# ETHERNET.net
KiCad netlist of a schematic drawn in Altium Designer
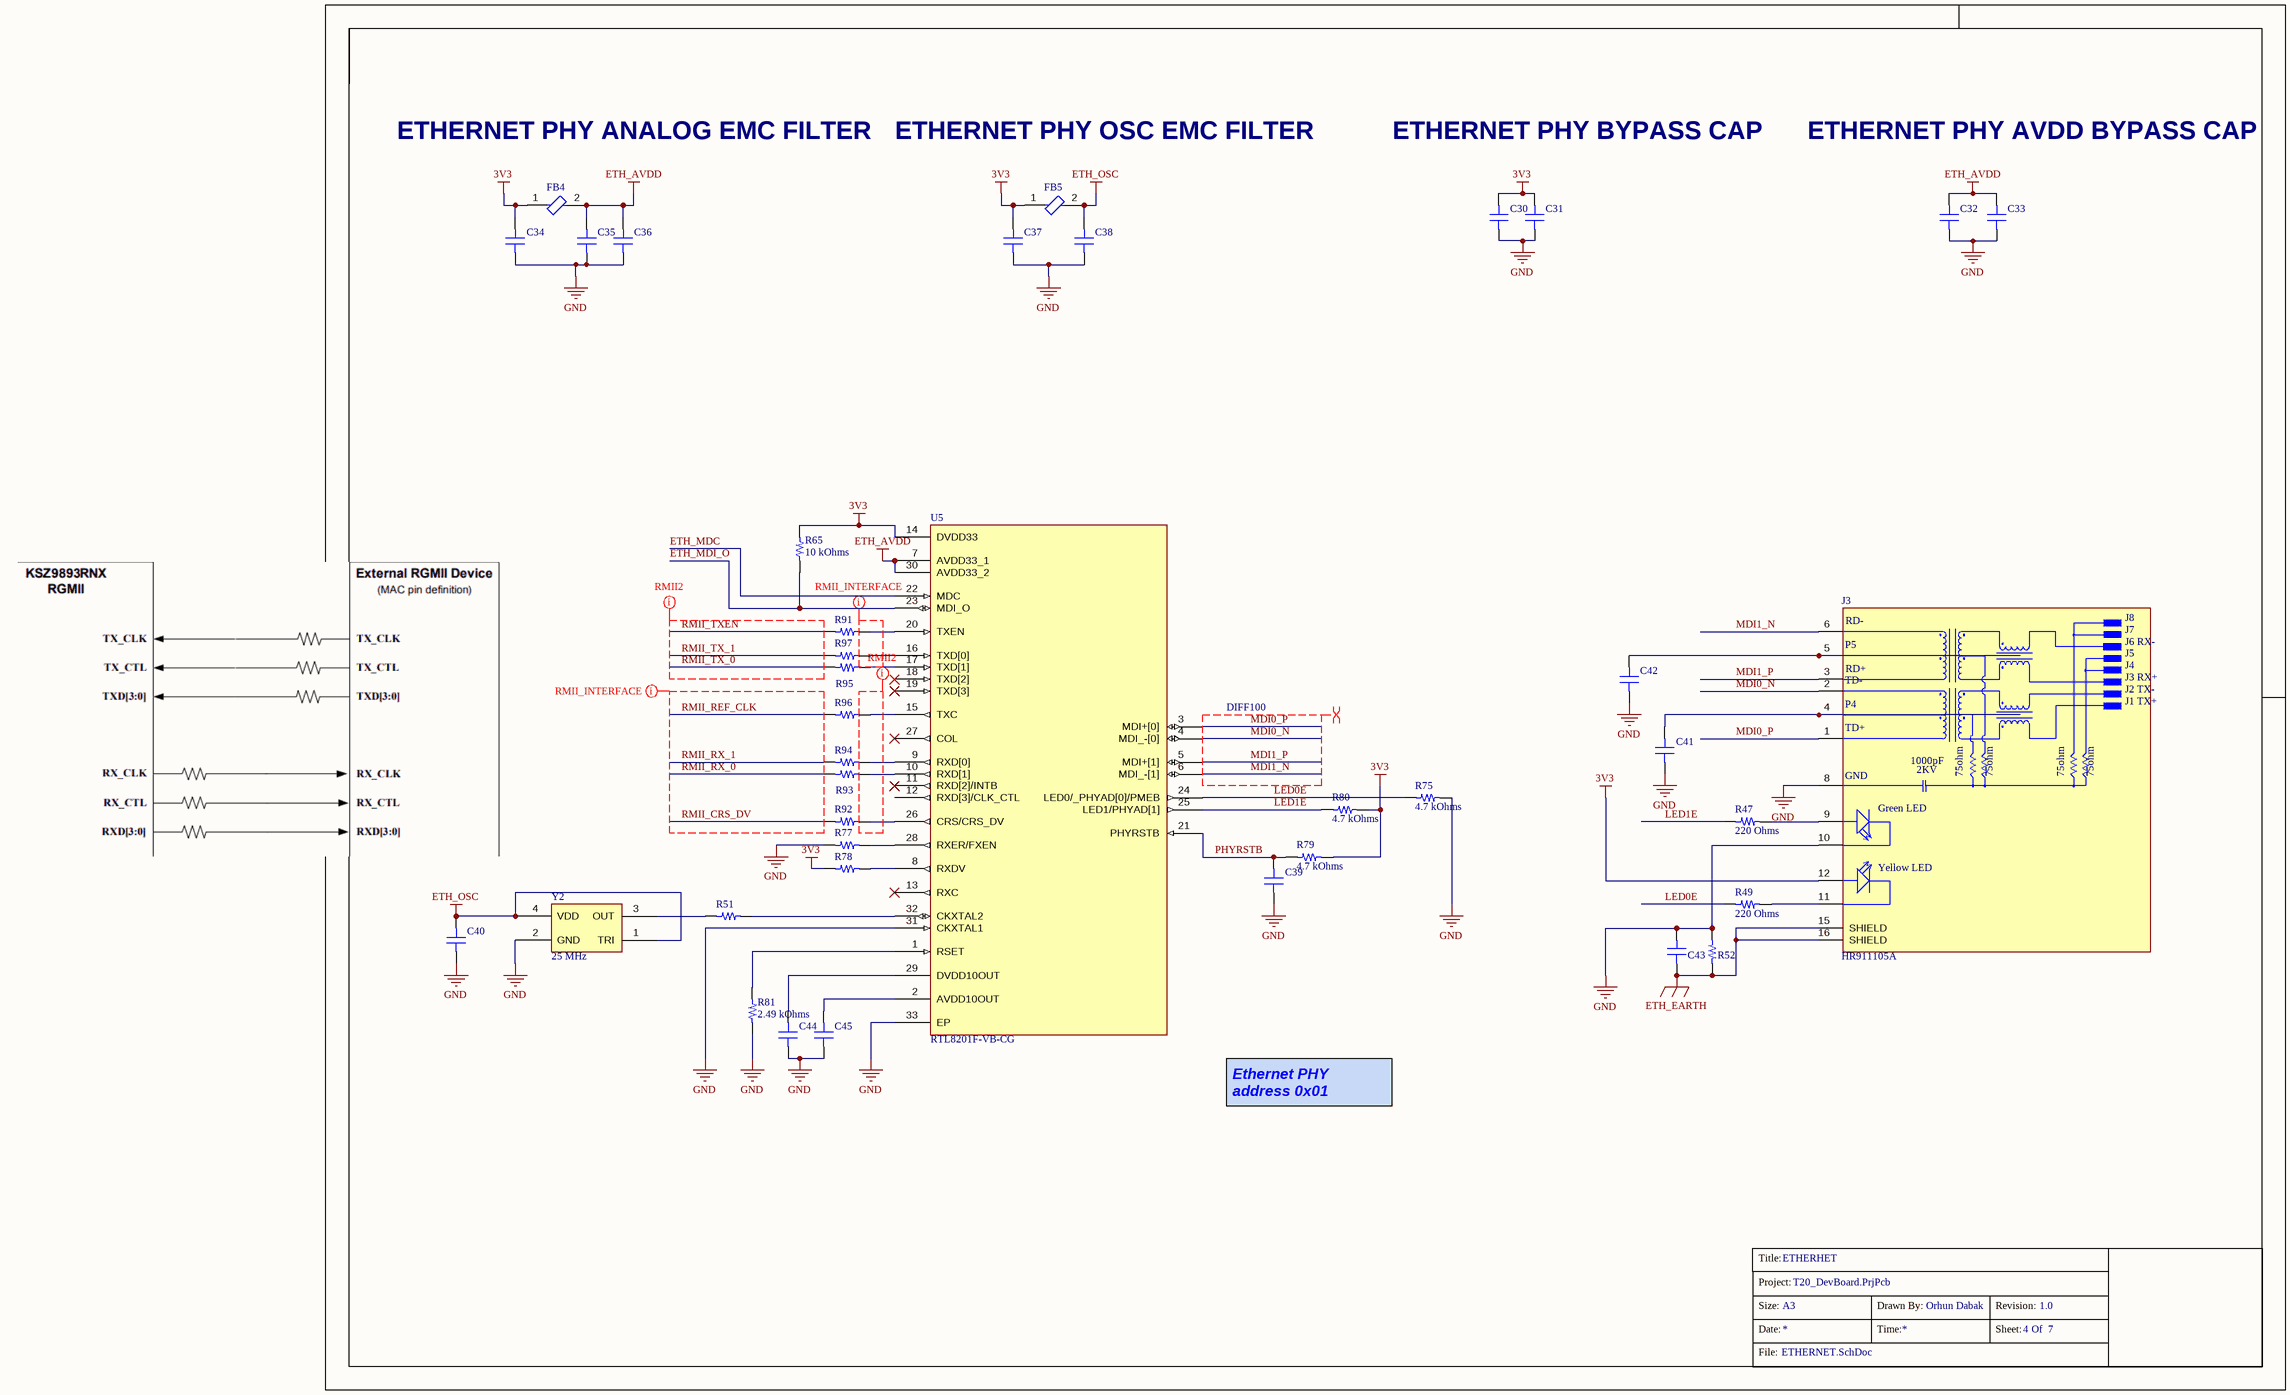
[diagram p0: ETHERNET.SchDoc]

(export (version "E")
  (design (tool "Eeschema 10.0.6"))
  (components
    (comp (ref "C30")
      (value "0.1 µF")
      (footprint "CAP 0402_1005")
      (description "CAP CER 0.1UF 10V X7R 0402")
      (fields (field (name "PART NUMBER") "CC0402KRX7R6BB104") (field (name "MANUFACTURER") "Yageo"))
      (libsource (lib "Celestial Altium Library - altium_library") (part "Capacitor"))
    )
    (comp (ref "C31")
      (value "2.2 µF")
      (footprint "CAP 0402_1005")
      (description "CAP CER 2.2UF 10V X5R 0402")
      (fields (field (name "PART NUMBER") "C0402C225M8PAC7867") (field (name "MANUFACTURER") "KEMET"))
      (libsource (lib "Celestial Altium Library - altium_library") (part "Capacitor"))
    )
    (comp (ref "C32")
      (value "0.1 µF")
      (footprint "CAP 0402_1005")
      (description "CAP CER 0.1UF 10V X7R 0402")
      (fields (field (name "PART NUMBER") "CC0402KRX7R6BB104") (field (name "MANUFACTURER") "Yageo"))
      (libsource (lib "Celestial Altium Library - altium_library") (part "Capacitor"))
    )
    (comp (ref "C33")
      (value "0.1 µF")
      (footprint "CAP 0402_1005")
      (description "CAP CER 0.1UF 10V X7R 0402")
      (fields (field (name "PART NUMBER") "CC0402KRX7R6BB104") (field (name "MANUFACTURER") "Yageo"))
      (libsource (lib "Celestial Altium Library - altium_library") (part "Capacitor"))
    )
    (comp (ref "C34")
      (value "0.1 µF")
      (footprint "CAP 0402_1005")
      (description "CAP CER 0.1UF 10V X7R 0402")
      (fields (field (name "PART NUMBER") "CC0402KRX7R6BB104") (field (name "MANUFACTURER") "Yageo"))
      (libsource (lib "Celestial Altium Library - altium_library") (part "Capacitor"))
    )
    (comp (ref "C35")
      (value "0.1 µF")
      (footprint "CAP 0402_1005")
      (description "CAP CER 0.1UF 10V X7R 0402")
      (fields (field (name "PART NUMBER") "CC0402KRX7R6BB104") (field (name "MANUFACTURER") "Yageo"))
      (libsource (lib "Celestial Altium Library - altium_library") (part "Capacitor"))
    )
    (comp (ref "C36")
      (value "4.7 µF")
      (footprint "CAP 0402_1005")
      (description "CAP CER 4.7UF 10V X5R 0402")
      (fields
        (field (name "PART NUMBER") "CL05A475MP5NRNC")
        (field (name "MANUFACTURER") "Samsung Electro-Mechanics")
      )
      (libsource (lib "Celestial Altium Library - altium_library") (part "Capacitor"))
    )
    (comp (ref "C37")
      (value "4.7 µF")
      (footprint "CAP 0402_1005")
      (description "CAP CER 4.7UF 10V X5R 0402")
      (fields
        (field (name "PART NUMBER") "CL05A475MP5NRNC")
        (field (name "MANUFACTURER") "Samsung Electro-Mechanics")
      )
      (libsource (lib "Celestial Altium Library - altium_library") (part "Capacitor"))
    )
    (comp (ref "C38")
      (value "4.7 µF")
      (footprint "CAP 0402_1005")
      (description "CAP CER 4.7UF 10V X5R 0402")
      (fields
        (field (name "PART NUMBER") "CL05A475MP5NRNC")
        (field (name "MANUFACTURER") "Samsung Electro-Mechanics")
      )
      (libsource (lib "Celestial Altium Library - altium_library") (part "Capacitor"))
    )
    (comp (ref "C39")
      (value "1000pF")
      (footprint "CAP 0402_1005")
      (description "CAP CER 1000PF 10V X7R 0402")
      (fields (field (name "PART NUMBER") "0402ZC102KAT2A") (field (name "MANUFACTURER") "AVX Corporation"))
      (libsource (lib "Celestial Altium Library - altium_library") (part "Capacitor"))
    )
    (comp (ref "C40")
      (value "0.1 µF")
      (footprint "CAP 0402_1005")
      (description "CAP CER 0.1UF 10V X7R 0402")
      (fields (field (name "PART NUMBER") "CC0402KRX7R6BB104") (field (name "MANUFACTURER") "Yageo"))
      (libsource (lib "Celestial Altium Library - altium_library") (part "Capacitor"))
    )
    (comp (ref "C41")
      (value "10000 pF")
      (footprint "CAP 0402_1005")
      (description "CAP CER 0402 10NF 50V X7R 10%")
      (fields (field (name "PART NUMBER") "C0402C103K5RECAUTO") (field (name "MANUFACTURER") "KEMET"))
      (libsource (lib "Celestial Altium Library - altium_library") (part "Capacitor"))
    )
    (comp (ref "C42")
      (value "10000 pF")
      (footprint "CAP 0402_1005")
      (description "CAP CER 0402 10NF 50V X7R 10%")
      (fields (field (name "PART NUMBER") "C0402C103K5RECAUTO") (field (name "MANUFACTURER") "KEMET"))
      (libsource (lib "Celestial Altium Library - altium_library") (part "Capacitor"))
    )
    (comp (ref "C43")
      (value "4700 pF")
      (footprint "CAP 0402_1005")
      (description "CAP CER 4700PF 100V X7R 0402")
      (fields
        (field (name "PART NUMBER") "GRM155R72A472KA01D")
        (field (name "MANUFACTURER") "Murata Electronics")
      )
      (libsource (lib "Celestial Altium Library - altium_library") (part "Capacitor"))
    )
    (comp (ref "C44")
      (value "0.1 µF")
      (footprint "CAP 0402_1005")
      (description "CAP CER 0.1UF 10V X7R 0402")
      (fields (field (name "PART NUMBER") "CC0402KRX7R6BB104") (field (name "MANUFACTURER") "Yageo"))
      (libsource (lib "Celestial Altium Library - altium_library") (part "Capacitor"))
    )
    (comp (ref "C45")
      (value "0.1 µF")
      (footprint "CAP 0402_1005")
      (description "CAP CER 0.1UF 10V X7R 0402")
      (fields (field (name "PART NUMBER") "CC0402KRX7R6BB104") (field (name "MANUFACTURER") "Yageo"))
      (libsource (lib "Celestial Altium Library - altium_library") (part "Capacitor"))
    )
    (comp (ref "FB4")
      (value "BLM15AX601SN1D")
      (footprint "FP-BLM15-0_05-IPC_B")
      (description "Chip Ferrite Bead, 0402, 600Ω @ 100MHz, 0.34Ω, 25%, 500mA")
      (fields (field (name "TOLERANCE") "25%"))
      (libsource (lib "Altium Content Vault") (part "5f30dd21d616792df468990f7003faa"))
    )
    (comp (ref "FB5")
      (value "BLM15AX601SN1D")
      (footprint "FP-BLM15-0_05-IPC_B")
      (description "Chip Ferrite Bead, 0402, 600Ω @ 100MHz, 0.34Ω, 25%, 500mA")
      (fields (field (name "TOLERANCE") "25%"))
      (libsource (lib "Altium Content Vault") (part "5f30dd21d616792df468990f7003faa"))
    )
    (comp (ref "J3")
      (value "HR911105A")
      (footprint "HANRUN_HR911105A:HANRUN_HR911105A")
      (description "DIP RJ45 Connector;")
      (libsource (lib "HR911105A") (part "HR911105A"))
    )
    (comp (ref "R47")
      (value "220 Ohms")
      (footprint "RES 0402_1005")
      (description "RES 220 OHM 1% 1/16W 0402")
      (fields (field (name "PART NUMBER") "RC0402FR-07220RL") (field (name "MANUFACTURER") "Yageo"))
      (libsource (lib "Celestial Altium Library - altium_library") (part "Resistor"))
    )
    (comp (ref "R49")
      (value "220 Ohms")
      (footprint "RES 0402_1005")
      (description "RES 220 OHM 1% 1/16W 0402")
      (fields (field (name "PART NUMBER") "RC0402FR-07220RL") (field (name "MANUFACTURER") "Yageo"))
      (libsource (lib "Celestial Altium Library - altium_library") (part "Resistor"))
    )
    (comp (ref "R51")
      (value "22 Ohms")
      (footprint "RES 0402_1005")
      (description "RES 22 OHM 1% 1/16W 0402")
      (fields (field (name "PART NUMBER") "RC0402FR-0722RL") (field (name "MANUFACTURER") "Yageo"))
      (libsource (lib "Celestial Altium Library - altium_library") (part "Resistor"))
    )
    (comp (ref "R52")
      (value "1 MOhms")
      (footprint "RES 0402_1005")
      (description "RES SMD 1M OHM 1% 1/16W 0402")
      (fields (field (name "PART NUMBER") "AC0402FR-071ML") (field (name "MANUFACTURER") "Yageo"))
      (libsource (lib "Celestial Altium Library - altium_library") (part "Resistor"))
    )
    (comp (ref "R65")
      (value "10 kOhms")
      (footprint "RES 0402_1005")
      (description "RES 10K OHM 0.1% 1/10W 0402")
      (fields
        (field (name "PART NUMBER") "RP73PF1E10KBTD")
        (field (name "MANUFACTURER") "TE Connectivity Passive Product")
      )
      (libsource (lib "Celestial Altium Library - altium_library") (part "Resistor"))
    )
    (comp (ref "R75")
      (value "4.7 kOhms")
      (footprint "RES 0402_1005")
      (description "RES SMD 4.7K OHM 1% 1/16W 0402")
      (fields (field (name "PART NUMBER") "RT0402FRE074K7L") (field (name "MANUFACTURER") "Yageo"))
      (libsource (lib "Celestial Altium Library - altium_library") (part "Resistor"))
    )
    (comp (ref "R77")
      (value "4.7 kOhms")
      (footprint "RES 0402_1005")
      (description "RES SMD 4.7K OHM 1% 1/16W 0402")
      (fields (field (name "PART NUMBER") "RT0402FRE074K7L") (field (name "MANUFACTURER") "Yageo"))
      (libsource (lib "Celestial Altium Library - altium_library") (part "Resistor"))
    )
    (comp (ref "R78")
      (value "10 kOhms")
      (footprint "RES 0402_1005")
      (description "RES 10K OHM 0.1% 1/10W 0402")
      (fields
        (field (name "PART NUMBER") "RP73PF1E10KBTD")
        (field (name "MANUFACTURER") "TE Connectivity Passive Product")
      )
      (libsource (lib "Celestial Altium Library - altium_library") (part "Resistor"))
    )
    (comp (ref "R79")
      (value "4.7 kOhms")
      (footprint "RES 0402_1005")
      (description "RES SMD 4.7K OHM 1% 1/16W 0402")
      (fields (field (name "PART NUMBER") "RT0402FRE074K7L") (field (name "MANUFACTURER") "Yageo"))
      (libsource (lib "Celestial Altium Library - altium_library") (part "Resistor"))
    )
    (comp (ref "R80")
      (value "4.7 kOhms")
      (footprint "RES 0402_1005")
      (description "RES SMD 4.7K OHM 1% 1/16W 0402")
      (fields (field (name "PART NUMBER") "RT0402FRE074K7L") (field (name "MANUFACTURER") "Yageo"))
      (libsource (lib "Celestial Altium Library - altium_library") (part "Resistor"))
    )
    (comp (ref "R81")
      (value "2.49 kOhms")
      (footprint "RES 0402_1005")
      (description "RES SMD 2.49KOHM 0.5% 1/16W 0402")
      (fields (field (name "PART NUMBER") "RR0510P-2491-D") (field (name "MANUFACTURER") "Susumu"))
      (libsource (lib "Celestial Altium Library - altium_library") (part "Resistor"))
    )
    (comp (ref "R91")
      (value "33 Ohms")
      (footprint "RES 0402_1005")
      (description "RES 33 OHM 1% 1/16W 0402")
      (fields (field (name "PART NUMBER") "RC0402FR-0733RL") (field (name "MANUFACTURER") "Yageo"))
      (libsource (lib "Celestial Altium Library - altium_library") (part "Resistor"))
    )
    (comp (ref "R92")
      (value "33 Ohms")
      (footprint "RES 0402_1005")
      (description "RES 33 OHM 1% 1/16W 0402")
      (fields (field (name "PART NUMBER") "RC0402FR-0733RL") (field (name "MANUFACTURER") "Yageo"))
      (libsource (lib "Celestial Altium Library - altium_library") (part "Resistor"))
    )
    (comp (ref "R93")
      (value "33 Ohms")
      (footprint "RES 0402_1005")
      (description "RES 33 OHM 1% 1/16W 0402")
      (fields (field (name "PART NUMBER") "RC0402FR-0733RL") (field (name "MANUFACTURER") "Yageo"))
      (libsource (lib "Celestial Altium Library - altium_library") (part "Resistor"))
    )
    (comp (ref "R94")
      (value "33 Ohms")
      (footprint "RES 0402_1005")
      (description "RES 33 OHM 1% 1/16W 0402")
      (fields (field (name "PART NUMBER") "RC0402FR-0733RL") (field (name "MANUFACTURER") "Yageo"))
      (libsource (lib "Celestial Altium Library - altium_library") (part "Resistor"))
    )
    (comp (ref "R95")
      (value "33 Ohms")
      (footprint "RES 0402_1005")
      (description "RES 33 OHM 1% 1/16W 0402")
      (fields (field (name "PART NUMBER") "RC0402FR-0733RL") (field (name "MANUFACTURER") "Yageo"))
      (libsource (lib "Celestial Altium Library - altium_library") (part "Resistor"))
    )
    (comp (ref "R96")
      (value "33 Ohms")
      (footprint "RES 0402_1005")
      (description "RES 33 OHM 1% 1/16W 0402")
      (fields (field (name "PART NUMBER") "RC0402FR-0733RL") (field (name "MANUFACTURER") "Yageo"))
      (libsource (lib "Celestial Altium Library - altium_library") (part "Resistor"))
    )
    (comp (ref "R97")
      (value "33 Ohms")
      (footprint "RES 0402_1005")
      (description "RES 33 OHM 1% 1/16W 0402")
      (fields (field (name "PART NUMBER") "RC0402FR-0733RL") (field (name "MANUFACTURER") "Yageo"))
      (libsource (lib "Celestial Altium Library - altium_library") (part "Resistor"))
    )
    (comp (ref "U5")
      (value "RTL8201F-VB-CG")
      (footprint "QFN50P500X500X100_HS-33N")
      (fields (field (name "MANUFACTURER") "Realtek Semicon"))
      (libsource (lib "T8_devkit_PCB") (part "RTL8201F-VB-CG"))
    )
    (comp (ref "Y2")
      (value "25 MHz")
      (footprint "ABRACON ASE")
      (description "XTAL OSC XO 25.0000MHZ CMOS SMD")
      (fields (field (name "PART NUMBER") "ASE-25.000MHZ-ET") (field (name "MANUFACTURER") "Abracon LLC"))
      (libsource (lib "Celestial Altium Library - altium_library") (part "Abracon XO ASE"))
    )
  )
  (nets
    (net (code "1") (name "/ETH_MDC") (class "Default")
      (node (ref "U5") (pin "22") (pinfunction "MDC_22") (pintype "input"))
    )
    (net (code "2") (name "/ETH_MDI_O") (class "Default")
      (node (ref "R65") (pin "2") (pinfunction "2_2") (pintype "passive"))
      (node (ref "U5") (pin "23") (pinfunction "MDI_O_23") (pintype "bidirectional"))
    )
    (net (code "3") (name "/LED0E") (class "Default")
      (node (ref "R49") (pin "2") (pinfunction "2_2") (pintype "passive"))
      (node (ref "R75") (pin "1") (pinfunction "1_1") (pintype "passive"))
      (node (ref "U5") (pin "24") (pinfunction "LED0/_PHYAD[0]/PMEB_24") (pintype "output"))
    )
    (net (code "4") (name "/LED1E") (class "Default")
      (node (ref "R47") (pin "2") (pinfunction "2_2") (pintype "passive"))
      (node (ref "R80") (pin "1") (pinfunction "1_1") (pintype "passive"))
      (node (ref "U5") (pin "25") (pinfunction "LED1/PHYAD[1]_25") (pintype "output"))
    )
    (net (code "5") (name "/MDI0_N") (class "Default")
      (node (ref "J3") (pin "2") (pinfunction "TD-_2") (pintype "passive"))
      (node (ref "U5") (pin "4") (pinfunction "MDI_-[0]_4") (pintype "bidirectional"))
    )
    (net (code "6") (name "/MDI0_P") (class "Default")
      (node (ref "J3") (pin "1") (pinfunction "TD+_1") (pintype "passive"))
      (node (ref "U5") (pin "3") (pinfunction "MDI+[0]_3") (pintype "bidirectional"))
    )
    (net (code "7") (name "/MDI1_N") (class "Default")
      (node (ref "J3") (pin "6") (pinfunction "RD-_6") (pintype "passive"))
      (node (ref "U5") (pin "6") (pinfunction "MDI_-[1]_6") (pintype "bidirectional"))
    )
    (net (code "8") (name "/MDI1_P") (class "Default")
      (node (ref "J3") (pin "3") (pinfunction "RD+_3") (pintype "passive"))
      (node (ref "U5") (pin "5") (pinfunction "MDI+[1]_5") (pintype "bidirectional"))
    )
    (net (code "9") (name "/PHYRSTB") (class "Default")
      (node (ref "C39") (pin "2") (pinfunction "2_2") (pintype "passive"))
      (node (ref "R79") (pin "1") (pinfunction "1_1") (pintype "passive"))
      (node (ref "U5") (pin "21") (pinfunction "PHYRSTB_21") (pintype "input"))
    )
    (net (code "10") (name "/RMII_CRS_DV") (class "Default")
      (node (ref "R92") (pin "1") (pinfunction "1_1") (pintype "passive"))
    )
    (net (code "11") (name "/RMII_REF_CLK") (class "Default")
      (node (ref "R96") (pin "1") (pinfunction "1_1") (pintype "passive"))
    )
    (net (code "12") (name "/RMII_RX_0") (class "Default")
      (node (ref "R93") (pin "1") (pinfunction "1_1") (pintype "passive"))
    )
    (net (code "13") (name "/RMII_RX_1") (class "Default")
      (node (ref "R94") (pin "1") (pinfunction "1_1") (pintype "passive"))
    )
    (net (code "14") (name "/RMII_TXEN") (class "Default")
      (node (ref "R91") (pin "1") (pinfunction "1_1") (pintype "passive"))
    )
    (net (code "15") (name "/RMII_TX_0") (class "Default")
      (node (ref "R95") (pin "1") (pinfunction "1_1") (pintype "passive"))
    )
    (net (code "16") (name "/RMII_TX_1") (class "Default")
      (node (ref "R97") (pin "1") (pinfunction "1_1") (pintype "passive"))
    )
    (net (code "17") (name "3V3") (class "Default")
      (node (ref "C30") (pin "2") (pinfunction "2_2") (pintype "passive"))
      (node (ref "C31") (pin "2") (pinfunction "2_2") (pintype "passive"))
      (node (ref "C34") (pin "2") (pinfunction "2_2") (pintype "passive"))
      (node (ref "C37") (pin "2") (pinfunction "2_2") (pintype "passive"))
      (node (ref "FB4") (pin "1") (pinfunction "1_1") (pintype "passive"))
      (node (ref "FB5") (pin "1") (pinfunction "1_1") (pintype "passive"))
      (node (ref "J3") (pin "12") (pinfunction "YA_12") (pintype "passive"))
      (node (ref "R65") (pin "1") (pinfunction "1_1") (pintype "passive"))
      (node (ref "R78") (pin "1") (pinfunction "1_1") (pintype "passive"))
      (node (ref "R79") (pin "2") (pinfunction "2_2") (pintype "passive"))
      (node (ref "R80") (pin "2") (pinfunction "2_2") (pintype "passive"))
      (node (ref "U5") (pin "14") (pinfunction "DVDD33_14") (pintype "power_in"))
    )
    (net (code "18") (name "ETH_AVDD") (class "Default")
      (node (ref "C32") (pin "2") (pinfunction "2_2") (pintype "passive"))
      (node (ref "C33") (pin "2") (pinfunction "2_2") (pintype "passive"))
      (node (ref "C35") (pin "2") (pinfunction "2_2") (pintype "passive"))
      (node (ref "C36") (pin "2") (pinfunction "2_2") (pintype "passive"))
      (node (ref "FB4") (pin "2") (pinfunction "2_2") (pintype "passive"))
      (node (ref "U5") (pin "30") (pinfunction "AVDD33_2_30") (pintype "power_in"))
      (node (ref "U5") (pin "7") (pinfunction "AVDD33_1_7") (pintype "power_in"))
    )
    (net (code "19") (name "ETH_EARTH") (class "Default")
      (node (ref "C43") (pin "1") (pinfunction "1_1") (pintype "passive"))
      (node (ref "J3") (pin "15") (pinfunction "SHIELD_15") (pintype "passive"))
      (node (ref "J3") (pin "16") (pinfunction "SHIELD_16") (pintype "passive"))
      (node (ref "R52") (pin "1") (pinfunction "1_1") (pintype "passive"))
    )
    (net (code "20") (name "ETH_OSC") (class "Default")
      (node (ref "C38") (pin "2") (pinfunction "2_2") (pintype "passive"))
      (node (ref "C40") (pin "2") (pinfunction "2_2") (pintype "passive"))
      (node (ref "FB5") (pin "2") (pinfunction "2_2") (pintype "passive"))
      (node (ref "Y2") (pin "1") (pinfunction "TRI_1") (pintype "passive"))
      (node (ref "Y2") (pin "4") (pinfunction "VDD_4") (pintype "passive"))
    )
    (net (code "21") (name "GND") (class "Default")
      (node (ref "C30") (pin "1") (pinfunction "1_1") (pintype "passive"))
      (node (ref "C31") (pin "1") (pinfunction "1_1") (pintype "passive"))
      (node (ref "C32") (pin "1") (pinfunction "1_1") (pintype "passive"))
      (node (ref "C33") (pin "1") (pinfunction "1_1") (pintype "passive"))
      (node (ref "C34") (pin "1") (pinfunction "1_1") (pintype "passive"))
      (node (ref "C35") (pin "1") (pinfunction "1_1") (pintype "passive"))
      (node (ref "C36") (pin "1") (pinfunction "1_1") (pintype "passive"))
      (node (ref "C37") (pin "1") (pinfunction "1_1") (pintype "passive"))
      (node (ref "C38") (pin "1") (pinfunction "1_1") (pintype "passive"))
      (node (ref "C39") (pin "1") (pinfunction "1_1") (pintype "passive"))
      (node (ref "C40") (pin "1") (pinfunction "1_1") (pintype "passive"))
      (node (ref "C41") (pin "1") (pinfunction "1_1") (pintype "passive"))
      (node (ref "C42") (pin "1") (pinfunction "1_1") (pintype "passive"))
      (node (ref "C43") (pin "2") (pinfunction "2_2") (pintype "passive"))
      (node (ref "C44") (pin "1") (pinfunction "1_1") (pintype "passive"))
      (node (ref "C45") (pin "1") (pinfunction "1_1") (pintype "passive"))
      (node (ref "J3") (pin "10") (pinfunction "GC_10") (pintype "passive"))
      (node (ref "J3") (pin "8") (pinfunction "GND_8") (pintype "power_in"))
      (node (ref "R52") (pin "2") (pinfunction "2_2") (pintype "passive"))
      (node (ref "R75") (pin "2") (pinfunction "2_2") (pintype "passive"))
      (node (ref "R77") (pin "1") (pinfunction "1_1") (pintype "passive"))
      (node (ref "R81") (pin "1") (pinfunction "1_1") (pintype "passive"))
      (node (ref "U5") (pin "31") (pinfunction "CKXTAL1_31") (pintype "input"))
      (node (ref "U5") (pin "33") (pinfunction "EP_33") (pintype "power_in"))
      (node (ref "Y2") (pin "2") (pinfunction "GND_2") (pintype "passive"))
    )
    (net (code "22") (name "Net-(J3-GA)") (class "Default")
      (node (ref "J3") (pin "9") (pinfunction "GA_9") (pintype "passive"))
      (node (ref "R47") (pin "1") (pinfunction "1_1") (pintype "passive"))
    )
    (net (code "23") (name "Net-(J3-P4)") (class "Default")
      (node (ref "C41") (pin "2") (pinfunction "2_2") (pintype "passive"))
      (node (ref "J3") (pin "4") (pinfunction "P4_4") (pintype "passive"))
    )
    (net (code "24") (name "Net-(J3-P5)") (class "Default")
      (node (ref "C42") (pin "2") (pinfunction "2_2") (pintype "passive"))
      (node (ref "J3") (pin "5") (pinfunction "P5_5") (pintype "passive"))
    )
    (net (code "25") (name "Net-(J3-YC)") (class "Default")
      (node (ref "J3") (pin "11") (pinfunction "YC_11") (pintype "passive"))
      (node (ref "R49") (pin "1") (pinfunction "1_1") (pintype "passive"))
    )
    (net (code "26") (name "Net-(U5-AVDD10OUT)") (class "Default")
      (node (ref "C45") (pin "2") (pinfunction "2_2") (pintype "passive"))
      (node (ref "U5") (pin "2") (pinfunction "AVDD10OUT_2") (pintype "power_in"))
    )
    (net (code "27") (name "Net-(U5-CKXTAL2)") (class "Default")
      (node (ref "R51") (pin "2") (pinfunction "2_2") (pintype "passive"))
      (node (ref "U5") (pin "32") (pinfunction "CKXTAL2_32") (pintype "bidirectional"))
    )
    (net (code "28") (name "Net-(U5-CRS{slash}CRS_DV)") (class "Default")
      (node (ref "R92") (pin "2") (pinfunction "2_2") (pintype "passive"))
      (node (ref "U5") (pin "26") (pinfunction "CRS/CRS_DV_26") (pintype "output"))
    )
    (net (code "29") (name "Net-(U5-DVDD10OUT)") (class "Default")
      (node (ref "C44") (pin "2") (pinfunction "2_2") (pintype "passive"))
      (node (ref "U5") (pin "29") (pinfunction "DVDD10OUT_29") (pintype "power_in"))
    )
    (net (code "30") (name "Net-(U5-RSET)") (class "Default")
      (node (ref "R81") (pin "2") (pinfunction "2_2") (pintype "passive"))
      (node (ref "U5") (pin "1") (pinfunction "RSET_1") (pintype "input"))
    )
    (net (code "31") (name "Net-(U5-RXDV)") (class "Default")
      (node (ref "R78") (pin "2") (pinfunction "2_2") (pintype "passive"))
      (node (ref "U5") (pin "8") (pinfunction "RXDV_8") (pintype "output"))
    )
    (net (code "32") (name "Net-(U5-RXD[0])") (class "Default")
      (node (ref "R94") (pin "2") (pinfunction "2_2") (pintype "passive"))
      (node (ref "U5") (pin "9") (pinfunction "RXD[0]_9") (pintype "output"))
    )
    (net (code "33") (name "Net-(U5-RXD[1])") (class "Default")
      (node (ref "R93") (pin "2") (pinfunction "2_2") (pintype "passive"))
      (node (ref "U5") (pin "10") (pinfunction "RXD[1]_10") (pintype "output"))
    )
    (net (code "34") (name "Net-(U5-RXER{slash}FXEN)") (class "Default")
      (node (ref "R77") (pin "2") (pinfunction "2_2") (pintype "passive"))
      (node (ref "U5") (pin "28") (pinfunction "RXER/FXEN_28") (pintype "output"))
    )
    (net (code "35") (name "Net-(U5-TXC)") (class "Default")
      (node (ref "R96") (pin "2") (pinfunction "2_2") (pintype "passive"))
      (node (ref "U5") (pin "15") (pinfunction "TXC_15") (pintype "output"))
    )
    (net (code "36") (name "Net-(U5-TXD[0])") (class "Default")
      (node (ref "R97") (pin "2") (pinfunction "2_2") (pintype "passive"))
      (node (ref "U5") (pin "16") (pinfunction "TXD[0]_16") (pintype "input"))
    )
    (net (code "37") (name "Net-(U5-TXD[1])") (class "Default")
      (node (ref "R95") (pin "2") (pinfunction "2_2") (pintype "passive"))
      (node (ref "U5") (pin "17") (pinfunction "TXD[1]_17") (pintype "input"))
    )
    (net (code "38") (name "Net-(U5-TXEN)") (class "Default")
      (node (ref "R91") (pin "2") (pinfunction "2_2") (pintype "passive"))
      (node (ref "U5") (pin "20") (pinfunction "TXEN_20") (pintype "input"))
    )
    (net (code "39") (name "Net-(Y2-OUT)") (class "Default")
      (node (ref "R51") (pin "1") (pinfunction "1_1") (pintype "passive"))
      (node (ref "Y2") (pin "3") (pinfunction "OUT_3") (pintype "passive"))
    )
    (net (code "40") (name "unconnected-(U5-COL-Pad27)") (class "Default")
      (node (ref "U5") (pin "27") (pinfunction "COL_27") (pintype "output+no_connect"))
    )
    (net (code "41") (name "unconnected-(U5-RXC-Pad13)") (class "Default")
      (node (ref "U5") (pin "13") (pinfunction "RXC_13") (pintype "output+no_connect"))
    )
    (net (code "42") (name "unconnected-(U5-RXD[2]{slash}INTB-Pad11)") (class "Default")
      (node (ref "U5") (pin "11") (pinfunction "RXD[2]/INTB_11") (pintype "output+no_connect"))
    )
    (net (code "43") (name "unconnected-(U5-RXD[3]{slash}CLK_CTL-Pad12)") (class "Default")
      (node (ref "U5") (pin "12") (pinfunction "RXD[3]/CLK_CTL_12") (pintype "output"))
    )
    (net (code "44") (name "unconnected-(U5-TXD[2]-Pad18)") (class "Default")
      (node (ref "U5") (pin "18") (pinfunction "TXD[2]_18") (pintype "input+no_connect"))
    )
    (net (code "45") (name "unconnected-(U5-TXD[3]-Pad19)") (class "Default")
      (node (ref "U5") (pin "19") (pinfunction "TXD[3]_19") (pintype "input+no_connect"))
    )
  )
)
